# LightSwitch.net
KiCad netlist of a schematic drawn in EAGLE
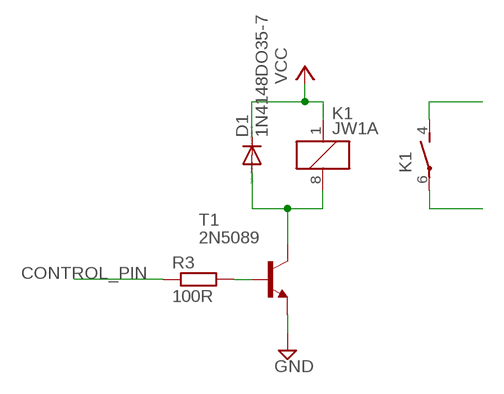
[diagram p0: schematic, sheet 1]

(export (version "E")
  (design (tool "Eeschema 10.0.6"))
  (components
    (comp (ref "D1")
      (value "1N4148DO35-7")
      (footprint "eagle-import:DO35-7")
      (libsource (lib "eagle-import") (part "1N4148DO35-7"))
    )
    (comp (ref "K1")
      (value "JW1A")
      (footprint "eagle-import:JW1A")
      (libsource (lib "eagle-import") (part "JW1A"))
    )
    (comp (ref "R3")
      (value "100R")
      (footprint "eagle-import:0204_5")
      (libsource (lib "eagle-import") (part "R-EU_0204/5"))
    )
    (comp (ref "T1")
      (value "2N5089")
      (footprint "eagle-import:TO92")
      (libsource (lib "eagle-import") (part "2N5089"))
    )
  )
  (nets
    (net (code "1") (name "/CONTROL_PIN") (class "Default")
      (node (ref "R3") (pin "1") (pinfunction "1_1") (pintype "passive"))
    )
    (net (code "2") (name "GND") (class "Default")
      (node (ref "T1") (pin "3") (pinfunction "E_3") (pintype "passive"))
    )
    (net (code "3") (name "Net-(K1B-2)") (class "Default")
      (node (ref "D1") (pin "A") (pinfunction "A_A") (pintype "passive"))
      (node (ref "K1") (pin "8") (pinfunction "2_8") (pintype "passive"))
      (node (ref "T1") (pin "1") (pinfunction "C_1") (pintype "passive"))
    )
    (net (code "4") (name "Net-(T1-B)") (class "Default")
      (node (ref "R3") (pin "2") (pinfunction "2_2") (pintype "passive"))
      (node (ref "T1") (pin "2") (pinfunction "B_2") (pintype "passive"))
    )
    (net (code "5") (name "VCC") (class "Default")
      (node (ref "D1") (pin "C") (pinfunction "C_C") (pintype "passive"))
      (node (ref "K1") (pin "1") (pinfunction "1_1") (pintype "passive"))
    )
    (net (code "6") (name "unconnected-(K1A-P-Pad6)") (class "Default")
      (node (ref "K1") (pin "6") (pinfunction "P_6") (pintype "passive"))
    )
    (net (code "7") (name "unconnected-(K1A-S-Pad4)") (class "Default")
      (node (ref "K1") (pin "4") (pinfunction "S_4") (pintype "passive"))
    )
  )
)
